# DCI_Ethernet.net
KiCad netlist of a schematic drawn in Altium Designer
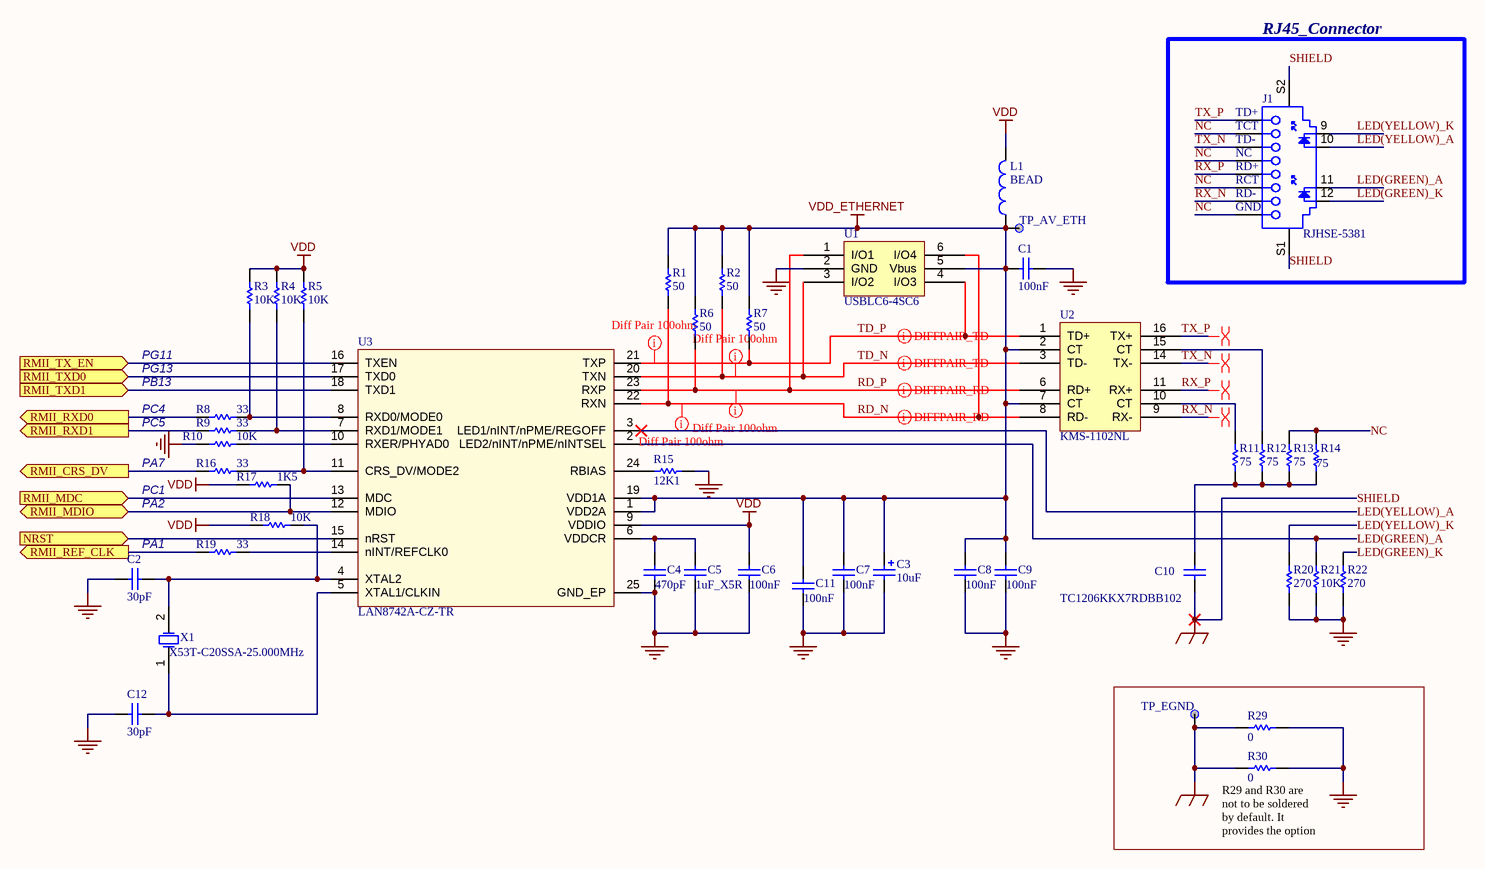
[diagram p0: DCI_Ethernet.SchDoc]

(export (version "E")
  (design (tool "Eeschema 10.0.6"))
  (components
    (comp (ref "C1")
      (value "100nF")
      (footprint "0603C")
      (description "Capacitor 0402 / 0603 / 0805")
      (libsource (lib "MCD_TOOLS") (part "Capacitor_ST"))
    )
    (comp (ref "C2")
      (value "30pF")
      (footprint "0603C")
      (description "Capacitor 0402 / 0603 / 0805")
      (libsource (lib "MCD_TOOLS") (part "Capacitor_ST"))
    )
    (comp (ref "C3")
      (value "10uF")
      (footprint "TAN-A - XDown")
      (description "Polarized Capacitor,10uF,10V,10%,typeA,VISHAY")
      (libsource (lib "MCD_TOOLS") (part "Cap_10uF_POL_10%_TANA"))
    )
    (comp (ref "C4")
      (value "470pF")
      (footprint "0603C")
      (description "Capacitor 0402 / 0603 / 0805")
      (libsource (lib "MCD_TOOLS") (part "Capacitor_ST"))
    )
    (comp (ref "C5")
      (value "1uF_X5R")
      (footprint "0603C")
      (description "0603  X5R 1µF")
      (fields (field (name "TOLERANCE") "10%"))
      (libsource (lib "MB963_1") (part "CAP SMD 0603  X5R 1µF 25V 10%"))
    )
    (comp (ref "C6")
      (value "100nF")
      (footprint "0603C")
      (description "Capacitor 0402 / 0603 / 0805")
      (libsource (lib "MCD_TOOLS") (part "Capacitor_ST"))
    )
    (comp (ref "C7")
      (value "100nF")
      (footprint "0603C")
      (description "Capacitor 0402 / 0603 / 0805")
      (libsource (lib "MCD_TOOLS") (part "Capacitor_ST"))
    )
    (comp (ref "C8")
      (value "100nF")
      (footprint "0603C")
      (description "Capacitor 0402 / 0603 / 0805")
      (libsource (lib "MCD_TOOLS") (part "Capacitor_ST"))
    )
    (comp (ref "C9")
      (value "100nF")
      (footprint "0603C")
      (description "Capacitor 0402 / 0603 / 0805")
      (libsource (lib "MCD_TOOLS") (part "Capacitor_ST"))
    )
    (comp (ref "C10")
      (value "TC1206KKX7RDBB102")
      (footprint "1206C")
      (description "Capacitor 0402 / 0603 / 0805/ 1206")
      (libsource (lib "MCD_TOOLS") (part "Capacitor_ST"))
    )
    (comp (ref "C11")
      (value "100nF")
      (footprint "0603C")
      (description "Capacitor 0402 / 0603 / 0805")
      (libsource (lib "MCD_TOOLS") (part "Capacitor_ST"))
    )
    (comp (ref "C12")
      (value "30pF")
      (footprint "0603C")
      (description "Capacitor 0402 / 0603 / 0805")
      (libsource (lib "MCD_TOOLS") (part "Capacitor_ST"))
    )
    (comp (ref "J1")
      (value "RJHSE-5381")
      (footprint "AMPH-RJHSE-5381_V")
      (fields (field (name "MANUFACTURER") "Amphenol"))
      (libsource (lib "Altium Content Vault") (part "RJ45-12-2SHLD"))
    )
    (comp (ref "L1")
      (value "BEAD")
      (footprint "0603L")
      (description "Inductor")
      (fields (field (name "PUBLISHER") "Altium Limited"))
      (libsource (lib "Miscellaneous Devices") (part "Inductor"))
    )
    (comp (ref "R1")
      (value "50")
      (footprint "0603R")
      (description "Resistor,50,0603,1%,YAGEO")
      (libsource (lib "MB1137") (part "Res_50_1%_0603"))
    )
    (comp (ref "R2")
      (value "50")
      (footprint "0603R")
      (description "Resistor,50,0603,1%,YAGEO")
      (libsource (lib "MB1137") (part "Res_50_1%_0603"))
    )
    (comp (ref "R3")
      (value "10K")
      (footprint "0603R")
      (description "Resistor 0402 / 0603 / 0805")
      (libsource (lib "Miscellaneous Devices") (part "Res1"))
    )
    (comp (ref "R4")
      (value "10K")
      (footprint "0603R")
      (description "Resistor 0402 / 0603 / 0805")
      (libsource (lib "Miscellaneous Devices") (part "Res1"))
    )
    (comp (ref "R5")
      (value "10K")
      (footprint "0603R")
      (description "Resistor 0402 / 0603 / 0805")
      (libsource (lib "Miscellaneous Devices") (part "Res1"))
    )
    (comp (ref "R6")
      (value "50")
      (footprint "0603R")
      (description "Resistor,50,0603,1%,YAGEO")
      (libsource (lib "MB1137") (part "Res_50_1%_0603"))
    )
    (comp (ref "R7")
      (value "50")
      (footprint "0603R")
      (description "Resistor,50,0603,1%,YAGEO")
      (libsource (lib "MB1137") (part "Res_50_1%_0603"))
    )
    (comp (ref "R8")
      (value "33")
      (footprint "0603R")
      (description "Resistor,33,0402,1%,YAGEO")
      (libsource (lib "MCD_TOOLS") (part "Res_33_1%_0402"))
    )
    (comp (ref "R9")
      (value "33")
      (footprint "0603R")
      (description "Resistor,33,0402,1%,YAGEO")
      (libsource (lib "MCD_TOOLS") (part "Res_33_1%_0402"))
    )
    (comp (ref "R10")
      (value "10K")
      (footprint "0603R")
      (description "Resistor 0402 / 0603 / 0805")
      (libsource (lib "Miscellaneous Devices") (part "Res1"))
    )
    (comp (ref "R11")
      (value "75")
      (footprint "0603R")
      (description "Resistor,75,0603,1%,YAGEO")
      (libsource (lib "MB1137") (part "Res_75_1%_0603"))
    )
    (comp (ref "R12")
      (value "75")
      (footprint "0603R")
      (description "Resistor,75,0603,1%,YAGEO")
      (libsource (lib "MB1137") (part "Res_75_1%_0603"))
    )
    (comp (ref "R13")
      (value "75")
      (footprint "0603R")
      (description "Resistor,75,0603,1%,YAGEO")
      (libsource (lib "MB1137") (part "Res_75_1%_0603"))
    )
    (comp (ref "R14")
      (value "75")
      (footprint "0603R")
      (description "Resistor,75,0603,1%,YAGEO")
      (libsource (lib "MB1137") (part "Res_75_1%_0603"))
    )
    (comp (ref "R15")
      (value "12K1")
      (footprint "0603R")
      (description "Resistor,12K1,0603,1%,VISHAY")
      (libsource (lib "MCD_TOOLS") (part "Res_12K1_1%_0603"))
    )
    (comp (ref "R16")
      (value "33")
      (footprint "0603R")
      (description "Resistor,33,0402,1%,YAGEO")
      (libsource (lib "MCD_TOOLS") (part "Res_33_1%_0402"))
    )
    (comp (ref "R17")
      (value "1K5")
      (footprint "0603R")
      (description "Resistor,1K5,0402,1%,YAGEO")
      (libsource (lib "MCD_TOOLS") (part "Res_1K5_1%_0402"))
    )
    (comp (ref "R18")
      (value "10K")
      (footprint "0603R")
      (description "Resistor 0402 / 0603 / 0805")
      (libsource (lib "Miscellaneous Devices") (part "Res1"))
    )
    (comp (ref "R19")
      (value "33")
      (footprint "0603R")
      (description "Resistor,33,0402,1%,YAGEO")
      (libsource (lib "MCD_TOOLS") (part "Res_33_1%_0402"))
    )
    (comp (ref "R20")
      (value "270")
      (footprint "0603R")
      (description "Resistor 0402 / 0603 / 0805")
      (libsource (lib "Miscellaneous Devices") (part "Res1"))
    )
    (comp (ref "R21")
      (value "10K")
      (footprint "0603R")
      (description "Resistor 0402 / 0603 / 0805")
      (libsource (lib "Miscellaneous Devices") (part "Res1"))
    )
    (comp (ref "R22")
      (value "270")
      (footprint "0603R")
      (description "Resistor 0402 / 0603 / 0805")
      (libsource (lib "Miscellaneous Devices") (part "Res1"))
    )
    (comp (ref "R29")
      (value "0")
      (footprint "0603R")
      (description "Resistor")
      (fields (field (name "PUBLISHER") "Altium Limited"))
      (libsource (lib "DCI_MB1137") (part "Res1"))
    )
    (comp (ref "R30")
      (value "0")
      (footprint "0603R")
      (description "Resistor")
      (fields (field (name "PUBLISHER") "Altium Limited"))
      (libsource (lib "DCI_MB1137") (part "Res1"))
    )
    (comp (ref "TP_AV_ETH") (value "TP_AVDD_ETH") (footprint "TP") (libsource (lib "*") (part "TP")))
    (comp (ref "TP_EGND") (value "TP_EGND") (footprint "TP") (libsource (lib "*") (part "TP")))
    (comp (ref "U1")
      (value "USBLC6-4SC6")
      (footprint "SOT23-6L")
      (libsource (lib "MB1137_1") (part "USBLC6-4SC6"))
    )
    (comp (ref "U2")
      (value "KMS-1102NL")
      (footprint "Transformer")
      (libsource (lib "MB1137") (part "KMS-1102NL"))
    )
    (comp (ref "U3")
      (value "LAN8742A-CZ-TR")
      (footprint "QFN24_0R5_4X4")
      (libsource (lib "MB1137") (part "LAN8742A-CZ-TR"))
    )
    (comp (ref "X1")
      (value "X53T-C20SSA-25.000MHz")
      (footprint "XTAL_2SM_5R0X3R2")
      (description "Crystal Oscillator")
      (fields (field (name "PUBLISHER") "Altium Limited"))
      (libsource (lib "MB1137") (part "XTAL_5032"))
    )
  )
  (nets
    (net (code "1") (name "/LED(GREEN)_A") (class "Default")
      (node (ref "J1") (pin "11") (pinfunction "11_11") (pintype "passive"))
      (node (ref "R21") (pin "1") (pinfunction "1_1") (pintype "passive"))
      (node (ref "U3") (pin "2") (pinfunction "LED2/nINT/nPME/nINTSEL_2") (pintype "passive"))
    )
    (net (code "2") (name "/LED(GREEN)_K") (class "Default")
      (node (ref "J1") (pin "12") (pinfunction "12_12") (pintype "passive"))
      (node (ref "R22") (pin "1") (pinfunction "1_1") (pintype "passive"))
    )
    (net (code "3") (name "/LED(YELLOW)_A") (class "Default")
      (node (ref "J1") (pin "10") (pinfunction "10_10") (pintype "passive"))
      (node (ref "U3") (pin "3") (pinfunction "LED1/nINT/nPME/REGOFF_3") (pintype "passive"))
    )
    (net (code "4") (name "/LED(YELLOW)_K") (class "Default")
      (node (ref "J1") (pin "9") (pinfunction "9_9") (pintype "passive"))
      (node (ref "R20") (pin "1") (pinfunction "1_1") (pintype "passive"))
    )
    (net (code "5") (name "/NC") (class "Default")
      (node (ref "J1") (pin "2") (pinfunction "TCT_2") (pintype "passive"))
      (node (ref "J1") (pin "4") (pinfunction "NC_4") (pintype "passive"))
      (node (ref "J1") (pin "6") (pinfunction "RCT_6") (pintype "passive"))
      (node (ref "J1") (pin "8") (pinfunction "GND_8") (pintype "passive"))
      (node (ref "R13") (pin "2") (pinfunction "2_2") (pintype "passive"))
      (node (ref "R14") (pin "2") (pinfunction "2_2") (pintype "passive"))
    )
    (net (code "6") (name "/NRST") (class "Default")
      (node (ref "U3") (pin "15") (pinfunction "nRST_15") (pintype "passive"))
    )
    (net (code "7") (name "/RD_N") (class "Default")
      (node (ref "R1") (pin "1") (pinfunction "1_1") (pintype "passive"))
      (node (ref "U1") (pin "6") (pinfunction "I/O4_6") (pintype "passive"))
      (node (ref "U2") (pin "8") (pinfunction "RD-_8") (pintype "passive"))
      (node (ref "U3") (pin "22") (pinfunction "RXN_22") (pintype "passive"))
    )
    (net (code "8") (name "/RD_P") (class "Default")
      (node (ref "R6") (pin "1") (pinfunction "1_1") (pintype "passive"))
      (node (ref "U1") (pin "1") (pinfunction "I/O1_1") (pintype "passive"))
      (node (ref "U2") (pin "6") (pinfunction "RD+_6") (pintype "passive"))
      (node (ref "U3") (pin "23") (pinfunction "RXP_23") (pintype "passive"))
    )
    (net (code "9") (name "/RMII_CRS_DV") (class "Default")
      (node (ref "R16") (pin "2") (pinfunction "2_2") (pintype "passive"))
    )
    (net (code "10") (name "/RMII_MDC") (class "Default")
      (node (ref "U3") (pin "13") (pinfunction "MDC_13") (pintype "passive"))
    )
    (net (code "11") (name "/RMII_MDIO") (class "Default")
      (node (ref "R17") (pin "1") (pinfunction "1_1") (pintype "passive"))
      (node (ref "U3") (pin "12") (pinfunction "MDIO_12") (pintype "passive"))
    )
    (net (code "12") (name "/RMII_REF_CLK") (class "Default")
      (node (ref "R19") (pin "2") (pinfunction "2_2") (pintype "passive"))
    )
    (net (code "13") (name "/RMII_RXD0") (class "Default")
      (node (ref "R8") (pin "2") (pinfunction "2_2") (pintype "passive"))
    )
    (net (code "14") (name "/RMII_RXD1") (class "Default")
      (node (ref "R9") (pin "2") (pinfunction "2_2") (pintype "passive"))
    )
    (net (code "15") (name "/RMII_TXD0") (class "Default")
      (node (ref "U3") (pin "17") (pinfunction "TXD0_17") (pintype "passive"))
    )
    (net (code "16") (name "/RMII_TXD1") (class "Default")
      (node (ref "U3") (pin "18") (pinfunction "TXD1_18") (pintype "passive"))
    )
    (net (code "17") (name "/RMII_TX_EN") (class "Default")
      (node (ref "U3") (pin "16") (pinfunction "TXEN_16") (pintype "passive"))
    )
    (net (code "18") (name "/RX_N") (class "Default")
      (node (ref "J1") (pin "7") (pinfunction "RD-_7") (pintype "passive"))
      (node (ref "U2") (pin "9") (pinfunction "RX-_9") (pintype "passive"))
    )
    (net (code "19") (name "/RX_P") (class "Default")
      (node (ref "J1") (pin "5") (pinfunction "RD+_5") (pintype "passive"))
      (node (ref "U2") (pin "11") (pinfunction "RX+_11") (pintype "passive"))
    )
    (net (code "20") (name "/TD_N") (class "Default")
      (node (ref "R2") (pin "1") (pinfunction "1_1") (pintype "passive"))
      (node (ref "U1") (pin "3") (pinfunction "I/O2_3") (pintype "passive"))
      (node (ref "U2") (pin "3") (pinfunction "TD-_3") (pintype "passive"))
      (node (ref "U3") (pin "20") (pinfunction "TXN_20") (pintype "passive"))
    )
    (net (code "21") (name "/TD_P") (class "Default")
      (node (ref "R7") (pin "1") (pinfunction "1_1") (pintype "passive"))
      (node (ref "U1") (pin "4") (pinfunction "I/O3_4") (pintype "passive"))
      (node (ref "U2") (pin "1") (pinfunction "TD+_1") (pintype "passive"))
      (node (ref "U3") (pin "21") (pinfunction "TXP_21") (pintype "passive"))
    )
    (net (code "22") (name "/TX_N") (class "Default")
      (node (ref "J1") (pin "3") (pinfunction "TD-_3") (pintype "passive"))
      (node (ref "U2") (pin "14") (pinfunction "TX-_14") (pintype "passive"))
    )
    (net (code "23") (name "/TX_P") (class "Default")
      (node (ref "J1") (pin "1") (pinfunction "TD+_1") (pintype "passive"))
      (node (ref "U2") (pin "16") (pinfunction "TX+_16") (pintype "passive"))
    )
    (net (code "24") (name "EGND") (class "Default")
      (node (ref "C10") (pin "1") (pinfunction "1_1") (pintype "passive"))
      (node (ref "J1") (pin "S1") (pinfunction "S1_S1") (pintype "passive"))
      (node (ref "J1") (pin "S2") (pinfunction "S2_S2") (pintype "passive"))
      (node (ref "R29") (pin "2") (pinfunction "2_2") (pintype "passive"))
      (node (ref "R30") (pin "2") (pinfunction "2_2") (pintype "passive"))
      (node (ref "TP_EGND") (pin "1") (pinfunction "1_1") (pintype "passive"))
    )
    (net (code "25") (name "GND") (class "Default")
      (node (ref "C1") (pin "1") (pinfunction "1_1") (pintype "passive"))
      (node (ref "C11") (pin "1") (pinfunction "1_1") (pintype "passive"))
      (node (ref "C12") (pin "2") (pinfunction "2_2") (pintype "passive"))
      (node (ref "C2") (pin "2") (pinfunction "2_2") (pintype "passive"))
      (node (ref "C3") (pin "2") (pinfunction "2_2") (pintype "passive"))
      (node (ref "C4") (pin "1") (pinfunction "1_1") (pintype "passive"))
      (node (ref "C5") (pin "2") (pinfunction "2_2") (pintype "passive"))
      (node (ref "C6") (pin "1") (pinfunction "1_1") (pintype "passive"))
      (node (ref "C7") (pin "1") (pinfunction "1_1") (pintype "passive"))
      (node (ref "C8") (pin "1") (pinfunction "1_1") (pintype "passive"))
      (node (ref "C9") (pin "1") (pinfunction "1_1") (pintype "passive"))
      (node (ref "R10") (pin "2") (pinfunction "2_2") (pintype "passive"))
      (node (ref "R15") (pin "2") (pinfunction "2_2") (pintype "passive"))
      (node (ref "R20") (pin "2") (pinfunction "2_2") (pintype "passive"))
      (node (ref "R21") (pin "2") (pinfunction "2_2") (pintype "passive"))
      (node (ref "R22") (pin "2") (pinfunction "2_2") (pintype "passive"))
      (node (ref "R29") (pin "1") (pinfunction "1_1") (pintype "passive"))
      (node (ref "R30") (pin "1") (pinfunction "1_1") (pintype "passive"))
      (node (ref "U1") (pin "2") (pinfunction "GND_2") (pintype "passive"))
      (node (ref "U3") (pin "25") (pinfunction "GND_EP_25") (pintype "passive"))
    )
    (net (code "26") (name "Net-(C10-Pad2)") (class "Default")
      (node (ref "C10") (pin "2") (pinfunction "2_2") (pintype "passive"))
      (node (ref "R11") (pin "1") (pinfunction "1_1") (pintype "passive"))
      (node (ref "R12") (pin "1") (pinfunction "1_1") (pintype "passive"))
      (node (ref "R13") (pin "1") (pinfunction "1_1") (pintype "passive"))
      (node (ref "R14") (pin "1") (pinfunction "1_1") (pintype "passive"))
    )
    (net (code "27") (name "Net-(R11-Pad2)") (class "Default")
      (node (ref "R11") (pin "2") (pinfunction "2_2") (pintype "passive"))
      (node (ref "U2") (pin "10") (pinfunction "CT_10") (pintype "passive"))
    )
    (net (code "28") (name "Net-(R12-Pad2)") (class "Default")
      (node (ref "R12") (pin "2") (pinfunction "2_2") (pintype "passive"))
      (node (ref "U2") (pin "15") (pinfunction "CT_15") (pintype "passive"))
    )
    (net (code "29") (name "Net-(U3-CRS_DV{slash}MODE2)") (class "Default")
      (node (ref "R16") (pin "1") (pinfunction "1_1") (pintype "passive"))
      (node (ref "R5") (pin "2") (pinfunction "2_2") (pintype "passive"))
      (node (ref "U3") (pin "11") (pinfunction "CRS_DV/MODE2_11") (pintype "passive"))
    )
    (net (code "30") (name "Net-(U3-RBIAS)") (class "Default")
      (node (ref "R15") (pin "1") (pinfunction "1_1") (pintype "passive"))
      (node (ref "U3") (pin "24") (pinfunction "RBIAS_24") (pintype "passive"))
    )
    (net (code "31") (name "Net-(U3-RXD0{slash}MODE0)") (class "Default")
      (node (ref "R3") (pin "2") (pinfunction "2_2") (pintype "passive"))
      (node (ref "R8") (pin "1") (pinfunction "1_1") (pintype "passive"))
      (node (ref "U3") (pin "8") (pinfunction "RXD0/MODE0_8") (pintype "passive"))
    )
    (net (code "32") (name "Net-(U3-RXD1{slash}MODE1)") (class "Default")
      (node (ref "R4") (pin "2") (pinfunction "2_2") (pintype "passive"))
      (node (ref "R9") (pin "1") (pinfunction "1_1") (pintype "passive"))
      (node (ref "U3") (pin "7") (pinfunction "RXD1/MODE1_7") (pintype "passive"))
    )
    (net (code "33") (name "Net-(U3-RXER{slash}PHYAD0)") (class "Default")
      (node (ref "R10") (pin "1") (pinfunction "1_1") (pintype "passive"))
      (node (ref "U3") (pin "10") (pinfunction "RXER/PHYAD0_10") (pintype "passive"))
    )
    (net (code "34") (name "Net-(U3-VDDCR)") (class "Default")
      (node (ref "C4") (pin "2") (pinfunction "2_2") (pintype "passive"))
      (node (ref "C5") (pin "1") (pinfunction "1_1") (pintype "passive"))
      (node (ref "U3") (pin "6") (pinfunction "VDDCR_6") (pintype "passive"))
    )
    (net (code "35") (name "Net-(U3-XTAL1{slash}CLKIN)") (class "Default")
      (node (ref "C12") (pin "1") (pinfunction "1_1") (pintype "passive"))
      (node (ref "U3") (pin "5") (pinfunction "XTAL1/CLKIN_5") (pintype "passive"))
      (node (ref "X1") (pin "1") (pinfunction "OSC1_1") (pintype "passive"))
    )
    (net (code "36") (name "Net-(U3-XTAL2)") (class "Default")
      (node (ref "C2") (pin "1") (pinfunction "1_1") (pintype "passive"))
      (node (ref "R18") (pin "2") (pinfunction "2_2") (pintype "passive"))
      (node (ref "U3") (pin "4") (pinfunction "XTAL2_4") (pintype "passive"))
      (node (ref "X1") (pin "2") (pinfunction "OSC2_2") (pintype "passive"))
    )
    (net (code "37") (name "Net-(U3-nINT{slash}REFCLK0)") (class "Default")
      (node (ref "R19") (pin "1") (pinfunction "1_1") (pintype "passive"))
      (node (ref "U3") (pin "14") (pinfunction "nINT/REFCLK0_14") (pintype "passive"))
    )
    (net (code "38") (name "VDD") (class "Default")
      (node (ref "C6") (pin "2") (pinfunction "2_2") (pintype "passive"))
      (node (ref "L1") (pin "2") (pinfunction "2_2") (pintype "passive"))
      (node (ref "R17") (pin "2") (pinfunction "2_2") (pintype "passive"))
      (node (ref "R18") (pin "1") (pinfunction "1_1") (pintype "passive"))
      (node (ref "R3") (pin "1") (pinfunction "1_1") (pintype "passive"))
      (node (ref "R4") (pin "1") (pinfunction "1_1") (pintype "passive"))
      (node (ref "R5") (pin "1") (pinfunction "1_1") (pintype "passive"))
      (node (ref "U3") (pin "9") (pinfunction "VDDIO_9") (pintype "passive"))
    )
    (net (code "39") (name "VDD_ETHERNET") (class "Default")
      (node (ref "C1") (pin "2") (pinfunction "2_2") (pintype "passive"))
      (node (ref "C11") (pin "2") (pinfunction "2_2") (pintype "passive"))
      (node (ref "C3") (pin "1") (pinfunction "1_1") (pintype "passive"))
      (node (ref "C7") (pin "2") (pinfunction "2_2") (pintype "passive"))
      (node (ref "C8") (pin "2") (pinfunction "2_2") (pintype "passive"))
      (node (ref "C9") (pin "2") (pinfunction "2_2") (pintype "passive"))
      (node (ref "L1") (pin "1") (pinfunction "1_1") (pintype "passive"))
      (node (ref "R1") (pin "2") (pinfunction "2_2") (pintype "passive"))
      (node (ref "R2") (pin "2") (pinfunction "2_2") (pintype "passive"))
      (node (ref "R6") (pin "2") (pinfunction "2_2") (pintype "passive"))
      (node (ref "R7") (pin "2") (pinfunction "2_2") (pintype "passive"))
      (node (ref "TP_AV_ETH") (pin "1") (pinfunction "1_1") (pintype "passive"))
      (node (ref "U1") (pin "5") (pinfunction "Vbus_5") (pintype "passive"))
      (node (ref "U2") (pin "2") (pinfunction "CT_2") (pintype "passive"))
      (node (ref "U2") (pin "7") (pinfunction "CT_7") (pintype "passive"))
      (node (ref "U3") (pin "1") (pinfunction "VDD2A_1") (pintype "passive"))
      (node (ref "U3") (pin "19") (pinfunction "VDD1A_19") (pintype "passive"))
    )
  )
)
